# CC3200_V2_0.net
KiCad netlist of a schematic drawn in EAGLE
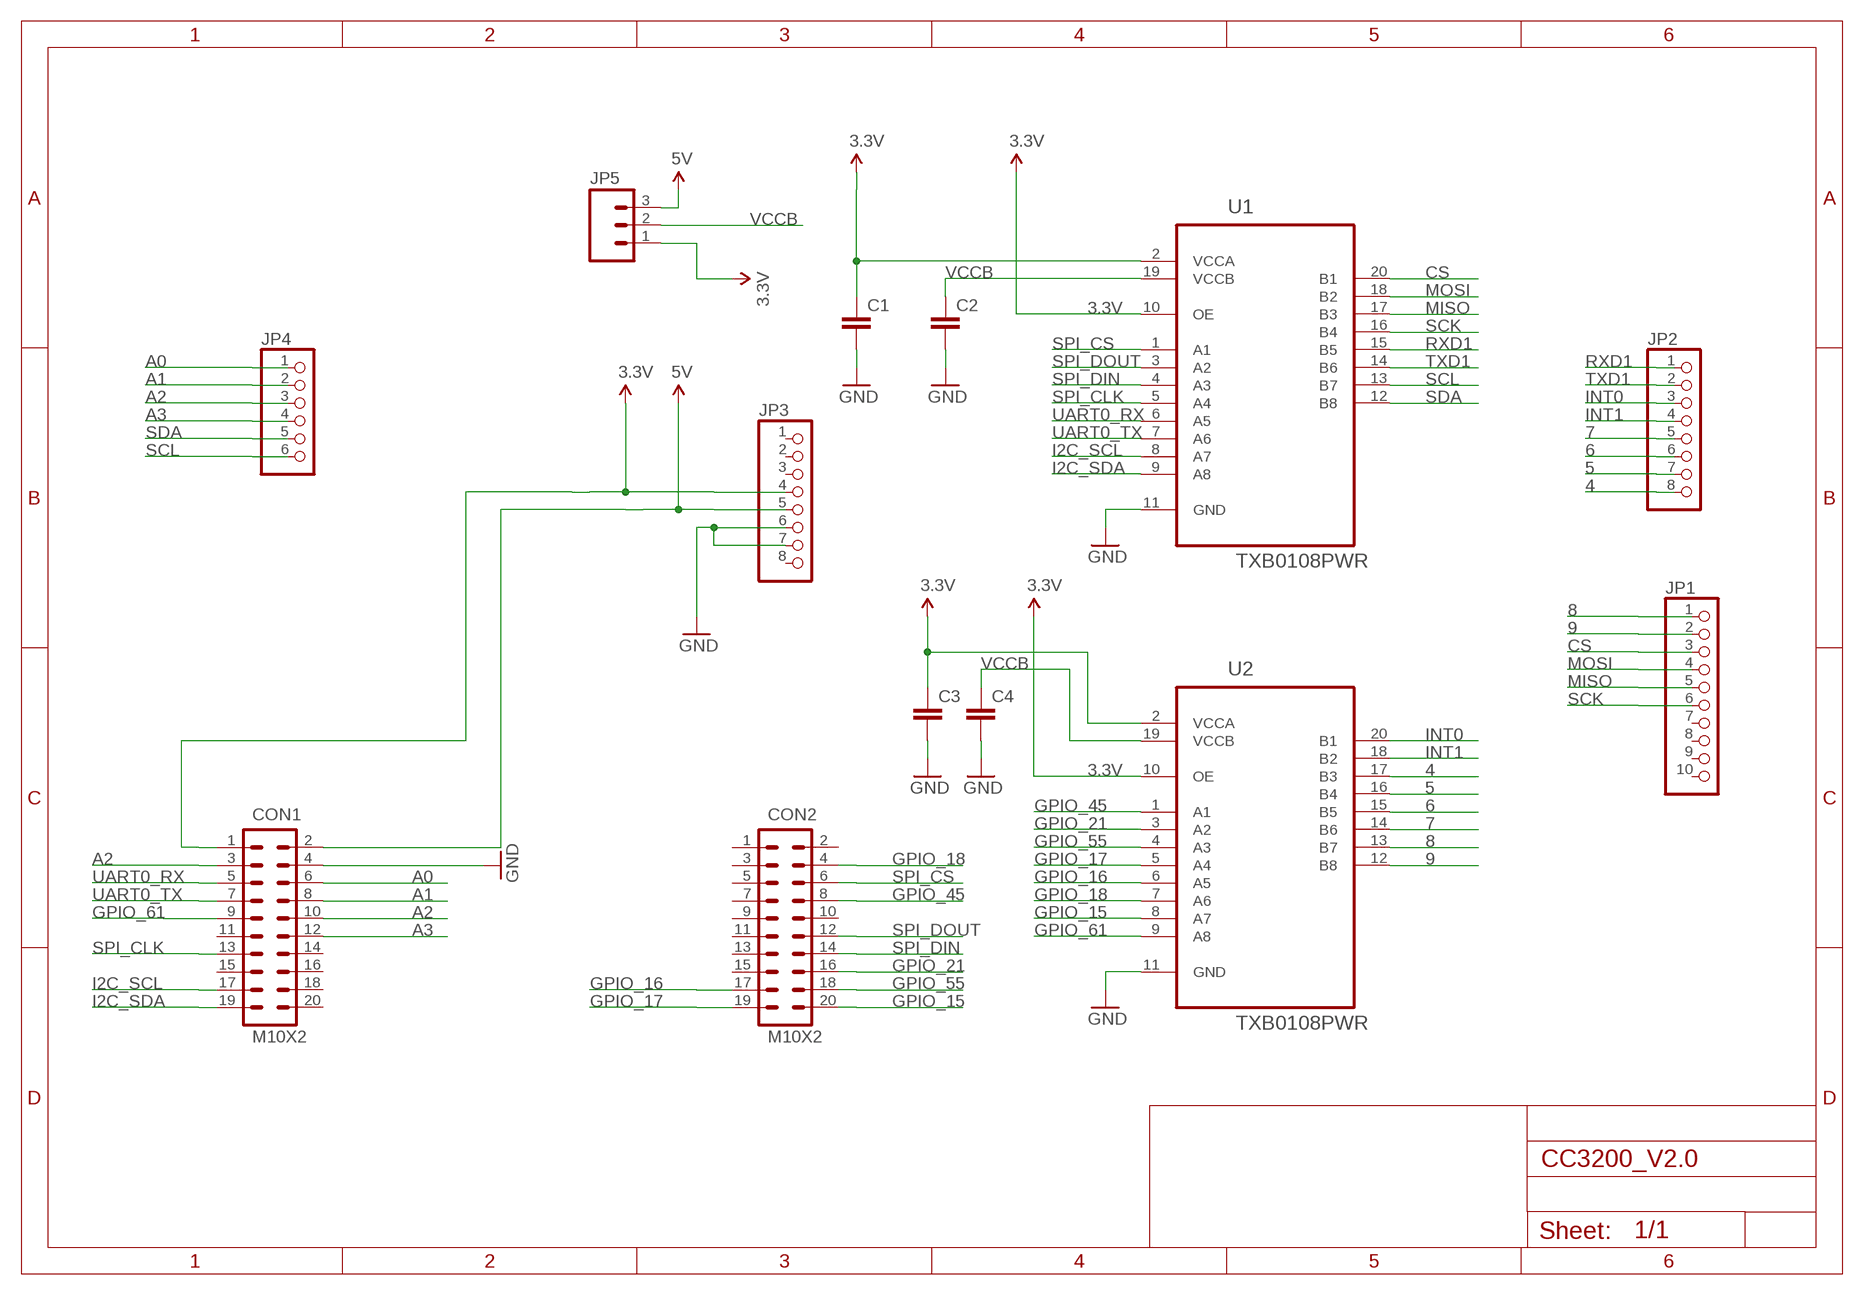
[diagram p0: schematic, sheet 1]

(export (version "E")
  (design (tool "Eeschema 10.0.6"))
  (components
    (comp (ref "C1")
      (value "C-EUC0805")
      (footprint "eagle-import:C0805")
      (libsource (lib "eagle-import") (part "C-EUC0805"))
    )
    (comp (ref "C2")
      (value "C-EUC0805")
      (footprint "eagle-import:C0805")
      (libsource (lib "eagle-import") (part "C-EUC0805"))
    )
    (comp (ref "C3")
      (value "C-EUC0805")
      (footprint "eagle-import:C0805")
      (libsource (lib "eagle-import") (part "C-EUC0805"))
    )
    (comp (ref "C4")
      (value "C-EUC0805")
      (footprint "eagle-import:C0805")
      (libsource (lib "eagle-import") (part "C-EUC0805"))
    )
    (comp (ref "CON1")
      (value "M10X2")
      (footprint "eagle-import:2X10")
      (libsource (lib "eagle-import") (part "M10X2"))
    )
    (comp (ref "CON2")
      (value "M10X2")
      (footprint "eagle-import:2X10")
      (libsource (lib "eagle-import") (part "M10X2"))
    )
    (comp (ref "JP1")
      (value "PINHD-1X10_ARD")
      (footprint "eagle-import:1X10")
      (libsource (lib "eagle-import") (part "PINHD-1X10_ARD"))
    )
    (comp (ref "JP2")
      (value "PINHD-1X8TH")
      (footprint "eagle-import:1X08-TH")
      (libsource (lib "eagle-import") (part "PINHD-1X8TH"))
    )
    (comp (ref "JP3")
      (value "PINHD-1X8TH")
      (footprint "eagle-import:1X08-TH")
      (libsource (lib "eagle-import") (part "PINHD-1X8TH"))
    )
    (comp (ref "JP4")
      (value "PINHD-1X6TH")
      (footprint "eagle-import:1X06-TH")
      (libsource (lib "eagle-import") (part "PINHD-1X6TH"))
    )
    (comp (ref "JP5")
      (value "M03PTH")
      (footprint "eagle-import:1X03")
      (libsource (lib "eagle-import") (part "M03PTH"))
    )
    (comp (ref "U1")
      (value "TXB0108PWR")
      (footprint "eagle-import:SOP65P640X120-20N")
      (libsource (lib "eagle-import") (part "TXB0108PWR"))
    )
    (comp (ref "U2")
      (value "TXB0108PWR")
      (footprint "eagle-import:SOP65P640X120-20N")
      (libsource (lib "eagle-import") (part "TXB0108PWR"))
    )
  )
  (nets
    (net (code "1") (name "/4") (class "Default")
      (node (ref "JP2") (pin "8") (pinfunction "8_8") (pintype "passive"))
      (node (ref "U2") (pin "17") (pinfunction "B3_17") (pintype "bidirectional"))
    )
    (net (code "2") (name "/5") (class "Default")
      (node (ref "JP2") (pin "7") (pinfunction "7_7") (pintype "passive"))
      (node (ref "U2") (pin "16") (pinfunction "B4_16") (pintype "bidirectional"))
    )
    (net (code "3") (name "/6") (class "Default")
      (node (ref "JP2") (pin "6") (pinfunction "6_6") (pintype "passive"))
      (node (ref "U2") (pin "15") (pinfunction "B5_15") (pintype "bidirectional"))
    )
    (net (code "4") (name "/7") (class "Default")
      (node (ref "JP2") (pin "5") (pinfunction "5_5") (pintype "passive"))
      (node (ref "U2") (pin "14") (pinfunction "B6_14") (pintype "bidirectional"))
    )
    (net (code "5") (name "/8") (class "Default")
      (node (ref "JP1") (pin "1") (pinfunction "1_1") (pintype "passive"))
      (node (ref "U2") (pin "13") (pinfunction "B7_13") (pintype "bidirectional"))
    )
    (net (code "6") (name "/9") (class "Default")
      (node (ref "JP1") (pin "2") (pinfunction "2_2") (pintype "passive"))
      (node (ref "U2") (pin "12") (pinfunction "B8_12") (pintype "bidirectional"))
    )
    (net (code "7") (name "/A0") (class "Default")
      (node (ref "CON1") (pin "6") (pinfunction "6_6") (pintype "passive"))
      (node (ref "JP4") (pin "1") (pinfunction "1_1") (pintype "passive"))
    )
    (net (code "8") (name "/A1") (class "Default")
      (node (ref "CON1") (pin "8") (pinfunction "8_8") (pintype "passive"))
      (node (ref "JP4") (pin "2") (pinfunction "2_2") (pintype "passive"))
    )
    (net (code "9") (name "/A2") (class "Default")
      (node (ref "CON1") (pin "10") (pinfunction "10_10") (pintype "passive"))
      (node (ref "CON1") (pin "3") (pinfunction "3_3") (pintype "passive"))
      (node (ref "JP4") (pin "3") (pinfunction "3_3") (pintype "passive"))
    )
    (net (code "10") (name "/A3") (class "Default")
      (node (ref "CON1") (pin "12") (pinfunction "12_12") (pintype "passive"))
      (node (ref "JP4") (pin "4") (pinfunction "4_4") (pintype "passive"))
    )
    (net (code "11") (name "/CS") (class "Default")
      (node (ref "JP1") (pin "3") (pinfunction "3_3") (pintype "passive"))
      (node (ref "U1") (pin "20") (pinfunction "B1_20") (pintype "bidirectional"))
    )
    (net (code "12") (name "/GPIO_15") (class "Default")
      (node (ref "CON2") (pin "20") (pinfunction "20_20") (pintype "passive"))
      (node (ref "U2") (pin "8") (pinfunction "A7_8") (pintype "bidirectional"))
    )
    (net (code "13") (name "/GPIO_16") (class "Default")
      (node (ref "CON2") (pin "17") (pinfunction "17_17") (pintype "passive"))
      (node (ref "U2") (pin "6") (pinfunction "A5_6") (pintype "bidirectional"))
    )
    (net (code "14") (name "/GPIO_17") (class "Default")
      (node (ref "CON2") (pin "19") (pinfunction "19_19") (pintype "passive"))
      (node (ref "U2") (pin "5") (pinfunction "A4_5") (pintype "bidirectional"))
    )
    (net (code "15") (name "/GPIO_18") (class "Default")
      (node (ref "CON2") (pin "4") (pinfunction "4_4") (pintype "passive"))
      (node (ref "U2") (pin "7") (pinfunction "A6_7") (pintype "bidirectional"))
    )
    (net (code "16") (name "/GPIO_21") (class "Default")
      (node (ref "CON2") (pin "16") (pinfunction "16_16") (pintype "passive"))
      (node (ref "U2") (pin "3") (pinfunction "A2_3") (pintype "bidirectional"))
    )
    (net (code "17") (name "/GPIO_45") (class "Default")
      (node (ref "CON2") (pin "8") (pinfunction "8_8") (pintype "passive"))
      (node (ref "U2") (pin "1") (pinfunction "A1_1") (pintype "bidirectional"))
    )
    (net (code "18") (name "/GPIO_55") (class "Default")
      (node (ref "CON2") (pin "18") (pinfunction "18_18") (pintype "passive"))
      (node (ref "U2") (pin "4") (pinfunction "A3_4") (pintype "bidirectional"))
    )
    (net (code "19") (name "/GPIO_61") (class "Default")
      (node (ref "CON1") (pin "9") (pinfunction "9_9") (pintype "passive"))
      (node (ref "U2") (pin "9") (pinfunction "A8_9") (pintype "bidirectional"))
    )
    (net (code "20") (name "/I2C_SCL") (class "Default")
      (node (ref "CON1") (pin "17") (pinfunction "17_17") (pintype "passive"))
      (node (ref "U1") (pin "8") (pinfunction "A7_8") (pintype "bidirectional"))
    )
    (net (code "21") (name "/I2C_SDA") (class "Default")
      (node (ref "CON1") (pin "19") (pinfunction "19_19") (pintype "passive"))
      (node (ref "U1") (pin "9") (pinfunction "A8_9") (pintype "bidirectional"))
    )
    (net (code "22") (name "/INT0") (class "Default")
      (node (ref "JP2") (pin "3") (pinfunction "3_3") (pintype "passive"))
      (node (ref "U2") (pin "20") (pinfunction "B1_20") (pintype "bidirectional"))
    )
    (net (code "23") (name "/INT1") (class "Default")
      (node (ref "JP2") (pin "4") (pinfunction "4_4") (pintype "passive"))
      (node (ref "U2") (pin "18") (pinfunction "B2_18") (pintype "bidirectional"))
    )
    (net (code "24") (name "/MISO") (class "Default")
      (node (ref "JP1") (pin "5") (pinfunction "5_5") (pintype "passive"))
      (node (ref "U1") (pin "17") (pinfunction "B3_17") (pintype "bidirectional"))
    )
    (net (code "25") (name "/MOSI") (class "Default")
      (node (ref "JP1") (pin "4") (pinfunction "4_4") (pintype "passive"))
      (node (ref "U1") (pin "18") (pinfunction "B2_18") (pintype "bidirectional"))
    )
    (net (code "26") (name "/RXD1") (class "Default")
      (node (ref "JP2") (pin "1") (pinfunction "1_1") (pintype "passive"))
      (node (ref "U1") (pin "15") (pinfunction "B5_15") (pintype "bidirectional"))
    )
    (net (code "27") (name "/SCK") (class "Default")
      (node (ref "JP1") (pin "6") (pinfunction "6_6") (pintype "passive"))
      (node (ref "U1") (pin "16") (pinfunction "B4_16") (pintype "bidirectional"))
    )
    (net (code "28") (name "/SCL") (class "Default")
      (node (ref "JP4") (pin "6") (pinfunction "6_6") (pintype "passive"))
      (node (ref "U1") (pin "13") (pinfunction "B7_13") (pintype "bidirectional"))
    )
    (net (code "29") (name "/SDA") (class "Default")
      (node (ref "JP4") (pin "5") (pinfunction "5_5") (pintype "passive"))
      (node (ref "U1") (pin "12") (pinfunction "B8_12") (pintype "bidirectional"))
    )
    (net (code "30") (name "/SPI_CLK") (class "Default")
      (node (ref "CON1") (pin "13") (pinfunction "13_13") (pintype "passive"))
      (node (ref "U1") (pin "5") (pinfunction "A4_5") (pintype "bidirectional"))
    )
    (net (code "31") (name "/SPI_CS") (class "Default")
      (node (ref "CON2") (pin "6") (pinfunction "6_6") (pintype "passive"))
      (node (ref "U1") (pin "1") (pinfunction "A1_1") (pintype "bidirectional"))
    )
    (net (code "32") (name "/SPI_DIN") (class "Default")
      (node (ref "CON2") (pin "14") (pinfunction "14_14") (pintype "passive"))
      (node (ref "U1") (pin "4") (pinfunction "A3_4") (pintype "bidirectional"))
    )
    (net (code "33") (name "/SPI_DOUT") (class "Default")
      (node (ref "CON2") (pin "12") (pinfunction "12_12") (pintype "passive"))
      (node (ref "U1") (pin "3") (pinfunction "A2_3") (pintype "bidirectional"))
    )
    (net (code "34") (name "/TXD1") (class "Default")
      (node (ref "JP2") (pin "2") (pinfunction "2_2") (pintype "passive"))
      (node (ref "U1") (pin "14") (pinfunction "B6_14") (pintype "bidirectional"))
    )
    (net (code "35") (name "/UART0_RX") (class "Default")
      (node (ref "CON1") (pin "5") (pinfunction "5_5") (pintype "passive"))
      (node (ref "U1") (pin "6") (pinfunction "A5_6") (pintype "bidirectional"))
    )
    (net (code "36") (name "/UART0_TX") (class "Default")
      (node (ref "CON1") (pin "7") (pinfunction "7_7") (pintype "passive"))
      (node (ref "U1") (pin "7") (pinfunction "A6_7") (pintype "bidirectional"))
    )
    (net (code "37") (name "/VCCB") (class "Default")
      (node (ref "C2") (pin "1") (pinfunction "1_1") (pintype "passive"))
      (node (ref "C4") (pin "1") (pinfunction "1_1") (pintype "passive"))
      (node (ref "JP5") (pin "2") (pinfunction "2_2") (pintype "passive"))
      (node (ref "U1") (pin "19") (pinfunction "VCCB_19") (pintype "power_in"))
      (node (ref "U2") (pin "19") (pinfunction "VCCB_19") (pintype "power_in"))
    )
    (net (code "38") (name "3.3V") (class "Default")
      (node (ref "C1") (pin "1") (pinfunction "1_1") (pintype "passive"))
      (node (ref "C3") (pin "1") (pinfunction "1_1") (pintype "passive"))
      (node (ref "CON1") (pin "1") (pinfunction "1_1") (pintype "passive"))
      (node (ref "JP3") (pin "4") (pinfunction "4_4") (pintype "passive"))
      (node (ref "JP5") (pin "1") (pinfunction "1_1") (pintype "passive"))
      (node (ref "U1") (pin "10") (pinfunction "OE_10") (pintype "input"))
      (node (ref "U1") (pin "2") (pinfunction "VCCA_2") (pintype "power_in"))
      (node (ref "U2") (pin "10") (pinfunction "OE_10") (pintype "input"))
      (node (ref "U2") (pin "2") (pinfunction "VCCA_2") (pintype "power_in"))
    )
    (net (code "39") (name "5V") (class "Default")
      (node (ref "CON1") (pin "2") (pinfunction "2_2") (pintype "passive"))
      (node (ref "JP3") (pin "5") (pinfunction "5_5") (pintype "passive"))
      (node (ref "JP5") (pin "3") (pinfunction "3_3") (pintype "passive"))
    )
    (net (code "40") (name "GND") (class "Default")
      (node (ref "C1") (pin "2") (pinfunction "2_2") (pintype "passive"))
      (node (ref "C2") (pin "2") (pinfunction "2_2") (pintype "passive"))
      (node (ref "C3") (pin "2") (pinfunction "2_2") (pintype "passive"))
      (node (ref "C4") (pin "2") (pinfunction "2_2") (pintype "passive"))
      (node (ref "CON1") (pin "4") (pinfunction "4_4") (pintype "passive"))
      (node (ref "JP3") (pin "6") (pinfunction "6_6") (pintype "passive"))
      (node (ref "JP3") (pin "7") (pinfunction "7_7") (pintype "passive"))
      (node (ref "U1") (pin "11") (pinfunction "GND_11") (pintype "passive"))
      (node (ref "U2") (pin "11") (pinfunction "GND_11") (pintype "passive"))
    )
    (net (code "41") (name "unconnected-(CON1-Pad11)") (class "Default")
      (node (ref "CON1") (pin "11") (pinfunction "11_11") (pintype "passive"))
    )
    (net (code "42") (name "unconnected-(CON1-Pad14)") (class "Default")
      (node (ref "CON1") (pin "14") (pinfunction "14_14") (pintype "passive"))
    )
    (net (code "43") (name "unconnected-(CON1-Pad15)") (class "Default")
      (node (ref "CON1") (pin "15") (pinfunction "15_15") (pintype "passive"))
    )
    (net (code "44") (name "unconnected-(CON1-Pad16)") (class "Default")
      (node (ref "CON1") (pin "16") (pinfunction "16_16") (pintype "passive"))
    )
    (net (code "45") (name "unconnected-(CON1-Pad18)") (class "Default")
      (node (ref "CON1") (pin "18") (pinfunction "18_18") (pintype "passive"))
    )
    (net (code "46") (name "unconnected-(CON1-Pad20)") (class "Default")
      (node (ref "CON1") (pin "20") (pinfunction "20_20") (pintype "passive"))
    )
    (net (code "47") (name "unconnected-(CON2-Pad1)") (class "Default")
      (node (ref "CON2") (pin "1") (pinfunction "1_1") (pintype "passive"))
    )
    (net (code "48") (name "unconnected-(CON2-Pad2)") (class "Default")
      (node (ref "CON2") (pin "2") (pinfunction "2_2") (pintype "passive"))
    )
    (net (code "49") (name "unconnected-(CON2-Pad3)") (class "Default")
      (node (ref "CON2") (pin "3") (pinfunction "3_3") (pintype "passive"))
    )
    (net (code "50") (name "unconnected-(CON2-Pad5)") (class "Default")
      (node (ref "CON2") (pin "5") (pinfunction "5_5") (pintype "passive"))
    )
    (net (code "51") (name "unconnected-(CON2-Pad7)") (class "Default")
      (node (ref "CON2") (pin "7") (pinfunction "7_7") (pintype "passive"))
    )
    (net (code "52") (name "unconnected-(CON2-Pad9)") (class "Default")
      (node (ref "CON2") (pin "9") (pinfunction "9_9") (pintype "passive"))
    )
    (net (code "53") (name "unconnected-(CON2-Pad10)") (class "Default")
      (node (ref "CON2") (pin "10") (pinfunction "10_10") (pintype "passive"))
    )
    (net (code "54") (name "unconnected-(CON2-Pad11)") (class "Default")
      (node (ref "CON2") (pin "11") (pinfunction "11_11") (pintype "passive"))
    )
    (net (code "55") (name "unconnected-(CON2-Pad13)") (class "Default")
      (node (ref "CON2") (pin "13") (pinfunction "13_13") (pintype "passive"))
    )
    (net (code "56") (name "unconnected-(CON2-Pad15)") (class "Default")
      (node (ref "CON2") (pin "15") (pinfunction "15_15") (pintype "passive"))
    )
    (net (code "57") (name "unconnected-(JP1-Pad7)") (class "Default")
      (node (ref "JP1") (pin "7") (pinfunction "7_7") (pintype "passive"))
    )
    (net (code "58") (name "unconnected-(JP1-Pad8)") (class "Default")
      (node (ref "JP1") (pin "8") (pinfunction "8_8") (pintype "passive"))
    )
    (net (code "59") (name "unconnected-(JP1-Pad9)") (class "Default")
      (node (ref "JP1") (pin "9") (pinfunction "9_9") (pintype "passive"))
    )
    (net (code "60") (name "unconnected-(JP1-Pad10)") (class "Default")
      (node (ref "JP1") (pin "10") (pinfunction "10_10") (pintype "passive"))
    )
    (net (code "61") (name "unconnected-(JP3-Pad1)") (class "Default")
      (node (ref "JP3") (pin "1") (pinfunction "1_1") (pintype "passive"))
    )
    (net (code "62") (name "unconnected-(JP3-Pad2)") (class "Default")
      (node (ref "JP3") (pin "2") (pinfunction "2_2") (pintype "passive"))
    )
    (net (code "63") (name "unconnected-(JP3-Pad3)") (class "Default")
      (node (ref "JP3") (pin "3") (pinfunction "3_3") (pintype "passive"))
    )
    (net (code "64") (name "unconnected-(JP3-Pad8)") (class "Default")
      (node (ref "JP3") (pin "8") (pinfunction "8_8") (pintype "passive"))
    )
  )
)
